# PIC32MK.net
KiCad netlist of a schematic drawn in Altium Designer
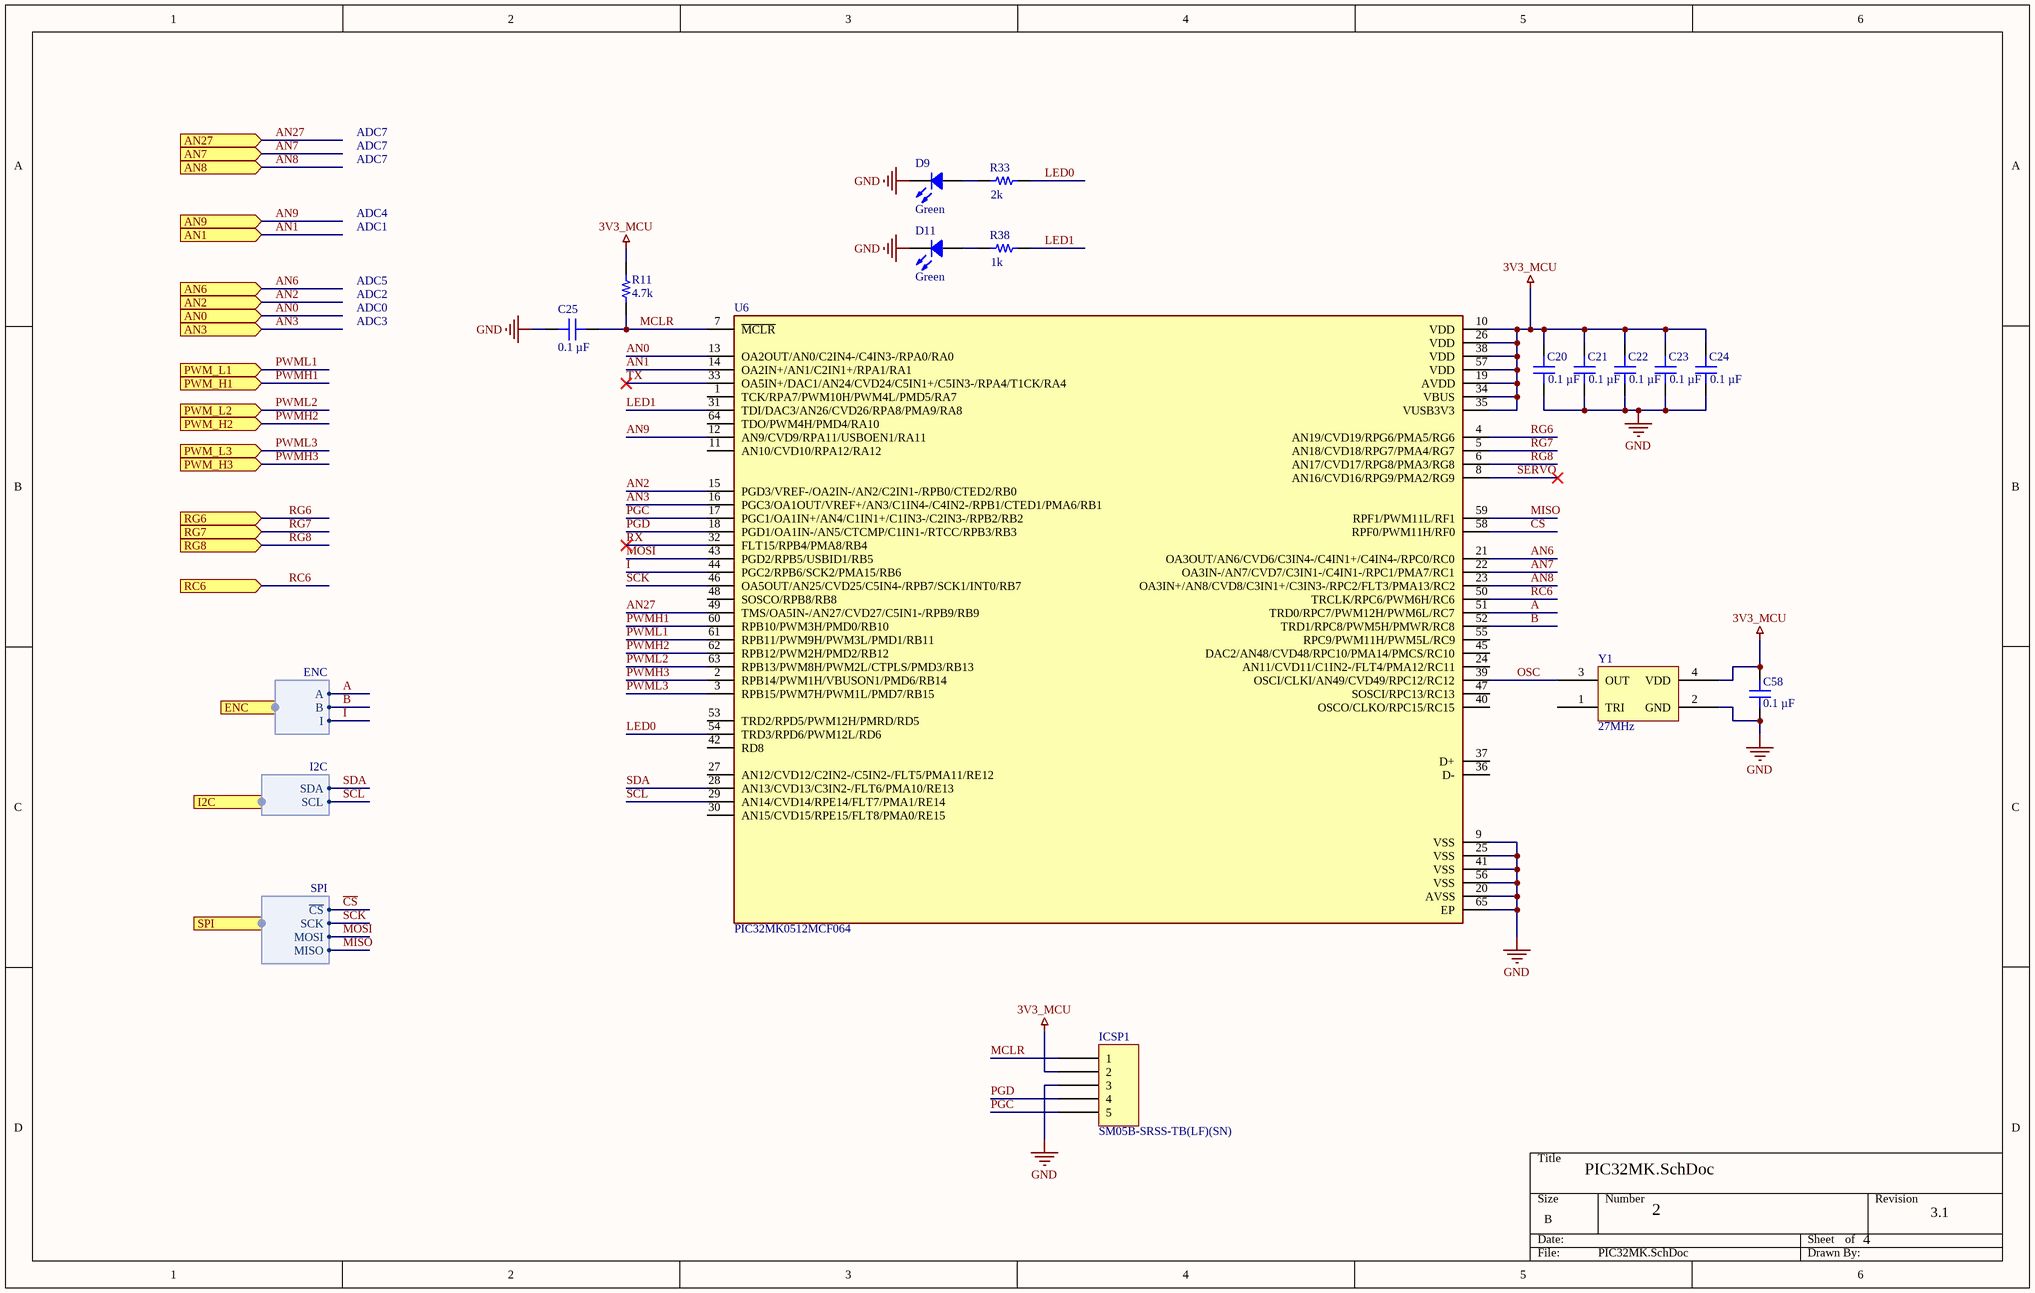
[diagram p0: PIC32MK.SchDoc]

(export (version "E")
  (design (tool "Eeschema 10.0.6"))
  (components
    (comp (ref "C20")
      (value "0.1 µF")
      (footprint "CAP 0402_1005")
      (description "CAP CER 0.1UF 16V X7R 0402")
      (fields (field (name "PART NUMBER") "C0402C104K4RACAUTO") (field (name "MANUFACTURER") "KEMET"))
      (libsource (lib "Celestial Altium Library - altium_library") (part "Capacitor"))
    )
    (comp (ref "C21")
      (value "0.1 µF")
      (footprint "CAP 0402_1005")
      (description "CAP CER 0.1UF 16V X7R 0402")
      (fields (field (name "PART NUMBER") "C0402C104K4RACAUTO") (field (name "MANUFACTURER") "KEMET"))
      (libsource (lib "Celestial Altium Library - altium_library") (part "Capacitor"))
    )
    (comp (ref "C22")
      (value "0.1 µF")
      (footprint "CAP 0402_1005")
      (description "CAP CER 0.1UF 16V X7R 0402")
      (fields (field (name "PART NUMBER") "C0402C104K4RACAUTO") (field (name "MANUFACTURER") "KEMET"))
      (libsource (lib "Celestial Altium Library - altium_library") (part "Capacitor"))
    )
    (comp (ref "C23")
      (value "0.1 µF")
      (footprint "CAP 0402_1005")
      (description "CAP CER 0.1UF 16V X7R 0402")
      (fields (field (name "PART NUMBER") "C0402C104K4RACAUTO") (field (name "MANUFACTURER") "KEMET"))
      (libsource (lib "Celestial Altium Library - altium_library") (part "Capacitor"))
    )
    (comp (ref "C24")
      (value "0.1 µF")
      (footprint "CAP 0402_1005")
      (description "CAP CER 0.1UF 16V X7R 0402")
      (fields (field (name "PART NUMBER") "C0402C104K4RACAUTO") (field (name "MANUFACTURER") "KEMET"))
      (libsource (lib "Celestial Altium Library - altium_library") (part "Capacitor"))
    )
    (comp (ref "C25")
      (value "0.1 µF")
      (footprint "CAP 0402_1005")
      (description "CAP CER 0.1UF 16V X7R 0402")
      (fields (field (name "PART NUMBER") "C0402C104K4RACAUTO") (field (name "MANUFACTURER") "KEMET"))
      (libsource (lib "Celestial Altium Library - altium_library") (part "Capacitor"))
    )
    (comp (ref "C58")
      (value "0.1 µF")
      (footprint "CAP 0402_1005")
      (description "CAP CER 0.1UF 16V X7R 0402")
      (fields (field (name "PART NUMBER") "C0402C104K4RACAUTO") (field (name "MANUFACTURER") "KEMET"))
      (libsource (lib "Celestial Altium Library - altium_library") (part "Capacitor"))
    )
    (comp (ref "D9")
      (value "Green")
      (footprint "LED 0603_1608 GREEN")
      (description "LED GREEN CLEAR 2SMD")
      (fields (field (name "PART NUMBER") "XZCDGK53W-8VF") (field (name "MANUFACTURER") "SunLED"))
      (libsource (lib "Celestial Altium Library - altium_library") (part "LED"))
    )
    (comp (ref "D11")
      (value "Green")
      (footprint "LED 0603_1608 GREEN")
      (description "LED GREEN CLEAR 2SMD")
      (fields (field (name "PART NUMBER") "XZCDGK53W-8VF") (field (name "MANUFACTURER") "SunLED"))
      (libsource (lib "Celestial Altium Library - altium_library") (part "LED"))
    )
    (comp (ref "ICSP1")
      (value "SM05B-SRSS-TB(LF)(SN)")
      (footprint "JST SM05B-SRSS-TB")
      (description "CONN HEADER SMD R/A 5POS 1MM")
      (fields (field (name "MANUFACTURER") "JST Sales America Inc."))
      (libsource (lib "Celestial Altium Library - altium_library") (part "5 Pin"))
    )
    (comp (ref "R11")
      (value "4.7k")
      (footprint "RES_0402")
      (description "RES 0402")
      (libsource (lib "IC") (part "RES_0402"))
    )
    (comp (ref "R33")
      (value "2k")
      (footprint "RES_0402")
      (description "RES 0402")
      (libsource (lib "IC") (part "RES_0402"))
    )
    (comp (ref "R38")
      (value "1k")
      (footprint "RES_0402")
      (description "RES 0402")
      (libsource (lib "IC") (part "RES_0402"))
    )
    (comp (ref "U6")
      (value "PIC32MK0512MCF064")
      (footprint "QFN50P900X900X100-65N")
      (description "PIC32MK Microcontroller IC 32-Bit 120MHz 1MB _1M x 8_ FLASH 64-TQFP _10x10_")
      (fields
        (field (name "MP") "PIC32MK1024MCF064-I/PT")
        (field (name "DIGI-KEY_PART_NUMBER") "PIC32MK1024MCF064-I/PT-ND")
      )
      (libsource (lib "IC") (part "PIC32MK0512MCF064"))
    )
    (comp (ref "Y1")
      (value "27MHz")
      (footprint "ABRACON ASD")
      (description "XTAL OSC XO 27.0000MHZ HCMOS SMD")
      (fields (field (name "PART NUMBER") "ASD3-27.000MHZ-EC-T") (field (name "MANUFACTURER") "Abracon LLC"))
      (libsource (lib "Celestial Altium Library - altium_library") (part "Abracon XO ASD"))
    )
  )
  (nets
    (net (code "4") (name "/A") (class "Default")
      (node (ref "U6") (pin "51") (pinfunction "TRD0/RPC7/PWM12H/PWM6L/RC7_51") (pintype "passive"))
    )
    (net (code "5") (name "/AN0") (class "Default")
      (node (ref "U6") (pin "13") (pinfunction "OA2OUT/AN0/C2IN4-/C4IN3-/RPA0/RA0_13") (pintype "passive"))
    )
    (net (code "6") (name "/AN1") (class "Default")
      (node (ref "U6") (pin "14") (pinfunction "OA2IN+/AN1/C2IN1+/RPA1/RA1_14") (pintype "passive"))
    )
    (net (code "7") (name "/AN2") (class "Default")
      (node (ref "U6") (pin "15") (pinfunction "PGD3/VREF-/OA2IN-/AN2/C2IN1-/RPB0/CTED2/RB0_15") (pintype "passive"))
    )
    (net (code "8") (name "/AN3") (class "Default")
      (node (ref "U6") (pin "16") (pinfunction "PGC3/OA1OUT/VREF+/AN3/C1IN4-/C4IN2-/RPB1/CTED1/PMA6/RB1_16") (pintype "passive"))
    )
    (net (code "9") (name "/AN6") (class "Default")
      (node (ref "U6") (pin "21") (pinfunction "OA3OUT/AN6/CVD6/C3IN4-/C4IN1+/C4IN4-/RPC0/RC0_21") (pintype "passive"))
    )
    (net (code "10") (name "/AN7") (class "Default")
      (node (ref "U6") (pin "22") (pinfunction "OA3IN-/AN7/CVD7/C3IN1-/C4IN1-/RPC1/PMA7/RC1_22") (pintype "passive"))
    )
    (net (code "11") (name "/AN8") (class "Default")
      (node (ref "U6") (pin "23") (pinfunction "OA3IN+/AN8/CVD8/C3IN1+/C3IN3-/RPC2/FLT3/PMA13/RC2_23") (pintype "passive"))
    )
    (net (code "12") (name "/AN9") (class "Default")
      (node (ref "U6") (pin "12") (pinfunction "AN9/CVD9/RPA11/USBOEN1/RA11_12") (pintype "passive"))
    )
    (net (code "13") (name "/AN27") (class "Default")
      (node (ref "U6") (pin "49") (pinfunction "TMS/OA5IN-/AN27/CVD27/C5IN1-/RPB9/RB9_49") (pintype "passive"))
    )
    (net (code "14") (name "/B") (class "Default")
      (node (ref "U6") (pin "52") (pinfunction "TRD1/RPC8/PWM5H/PMWR/RC8_52") (pintype "passive"))
    )
    (net (code "15") (name "/I") (class "Default")
      (node (ref "U6") (pin "44") (pinfunction "PGC2/RPB6/SCK2/PMA15/RB6_44") (pintype "passive"))
    )
    (net (code "16") (name "/LED0") (class "Default")
      (node (ref "R33") (pin "2") (pinfunction "2_2") (pintype "passive"))
      (node (ref "U6") (pin "54") (pinfunction "TRD3/RPD6/PWM12L/RD6_54") (pintype "passive"))
    )
    (net (code "17") (name "/LED1") (class "Default")
      (node (ref "R38") (pin "2") (pinfunction "2_2") (pintype "passive"))
      (node (ref "U6") (pin "31") (pinfunction "TDI/DAC3/AN26/CVD26/RPA8/PMA9/RA8_31") (pintype "passive"))
    )
    (net (code "18") (name "/MCLR") (class "Default")
      (node (ref "C25") (pin "1") (pinfunction "1_1") (pintype "passive"))
      (node (ref "ICSP1") (pin "1") (pinfunction "1_1") (pintype "passive"))
      (node (ref "R11") (pin "1") (pinfunction "1_1") (pintype "passive"))
      (node (ref "U6") (pin "7") (pinfunction "~{MCLR}_7") (pintype "passive"))
    )
    (net (code "19") (name "/MISO") (class "Default")
      (node (ref "U6") (pin "59") (pinfunction "RPF1/PWM11L/RF1_59") (pintype "passive"))
    )
    (net (code "20") (name "/MOSI") (class "Default")
      (node (ref "U6") (pin "43") (pinfunction "PGD2/RPB5/USBID1/RB5_43") (pintype "passive"))
    )
    (net (code "21") (name "/OSC") (class "Default")
      (node (ref "U6") (pin "39") (pinfunction "OSCI/CLKI/AN49/CVD49/RPC12/RC12_39") (pintype "passive"))
      (node (ref "Y1") (pin "3") (pinfunction "OUT_3") (pintype "passive"))
    )
    (net (code "22") (name "/PGC") (class "Default")
      (node (ref "ICSP1") (pin "5") (pinfunction "5_5") (pintype "passive"))
      (node (ref "U6") (pin "17") (pinfunction "PGC1/OA1IN+/AN4/C1IN1+/C1IN3-/C2IN3-/RPB2/RB2_17") (pintype "passive"))
    )
    (net (code "23") (name "/PGD") (class "Default")
      (node (ref "ICSP1") (pin "4") (pinfunction "4_4") (pintype "passive"))
      (node (ref "U6") (pin "18") (pinfunction "PGD1/OA1IN-/AN5/CTCMP/C1IN1-/RTCC/RPB3/RB3_18") (pintype "passive"))
    )
    (net (code "24") (name "/PWMH1") (class "Default")
      (node (ref "U6") (pin "60") (pinfunction "RPB10/PWM3H/PMD0/RB10_60") (pintype "passive"))
    )
    (net (code "25") (name "/PWMH2") (class "Default")
      (node (ref "U6") (pin "62") (pinfunction "RPB12/PWM2H/PMD2/RB12_62") (pintype "passive"))
    )
    (net (code "26") (name "/PWMH3") (class "Default")
      (node (ref "U6") (pin "2") (pinfunction "RPB14/PWM1H/VBUSON1/PMD6/RB14_2") (pintype "passive"))
    )
    (net (code "27") (name "/PWML1") (class "Default")
      (node (ref "U6") (pin "61") (pinfunction "RPB11/PWM9H/PWM3L/PMD1/RB11_61") (pintype "passive"))
    )
    (net (code "28") (name "/PWML2") (class "Default")
      (node (ref "U6") (pin "63") (pinfunction "RPB13/PWM8H/PWM2L/CTPLS/PMD3/RB13_63") (pintype "passive"))
    )
    (net (code "29") (name "/PWML3") (class "Default")
      (node (ref "U6") (pin "3") (pinfunction "RPB15/PWM7H/PWM1L/PMD7/RB15_3") (pintype "passive"))
    )
    (net (code "30") (name "/RC6") (class "Default")
      (node (ref "U6") (pin "50") (pinfunction "TRCLK/RPC6/PWM6H/RC6_50") (pintype "passive"))
    )
    (net (code "31") (name "/RG6") (class "Default")
      (node (ref "U6") (pin "4") (pinfunction "AN19/CVD19/RPG6/PMA5/RG6_4") (pintype "passive"))
    )
    (net (code "32") (name "/RG7") (class "Default")
      (node (ref "U6") (pin "5") (pinfunction "AN18/CVD18/RPG7/PMA4/RG7_5") (pintype "passive"))
    )
    (net (code "33") (name "/RG8") (class "Default")
      (node (ref "U6") (pin "6") (pinfunction "AN17/CVD17/RPG8/PMA3/RG8_6") (pintype "passive"))
    )
    (net (code "34") (name "/RX") (class "Default")
      (node (ref "U6") (pin "32") (pinfunction "FLT15/RPB4/PMA8/RB4_32") (pintype "passive+no_connect"))
    )
    (net (code "35") (name "/SCK") (class "Default")
      (node (ref "U6") (pin "46") (pinfunction "OA5OUT/AN25/CVD25/C5IN4-/RPB7/SCK1/INT0/RB7_46") (pintype "passive"))
    )
    (net (code "36") (name "/SCL") (class "Default")
      (node (ref "U6") (pin "29") (pinfunction "AN14/CVD14/RPE14/FLT7/PMA1/RE14_29") (pintype "passive"))
    )
    (net (code "37") (name "/SDA") (class "Default")
      (node (ref "U6") (pin "28") (pinfunction "AN13/CVD13/C3IN2-/FLT6/PMA10/RE13_28") (pintype "passive"))
    )
    (net (code "38") (name "/SERVO") (class "Default")
      (node (ref "U6") (pin "8") (pinfunction "AN16/CVD16/RPG9/PMA2/RG9_8") (pintype "passive+no_connect"))
    )
    (net (code "39") (name "/TX") (class "Default")
      (node (ref "U6") (pin "33") (pinfunction "OA5IN+/DAC1/AN24/CVD24/C5IN1+/C5IN3-/RPA4/T1CK/RA4_33") (pintype "passive+no_connect"))
    )
    (net (code "43") (name "/~{CS}") (class "Default")
      (node (ref "U6") (pin "58") (pinfunction "RPF0/PWM11H/RF0_58") (pintype "passive"))
    )
    (net (code "44") (name "3V3_MCU") (class "Default")
      (node (ref "C20") (pin "2") (pinfunction "2_2") (pintype "passive"))
      (node (ref "C21") (pin "2") (pinfunction "2_2") (pintype "passive"))
      (node (ref "C22") (pin "2") (pinfunction "2_2") (pintype "passive"))
      (node (ref "C23") (pin "2") (pinfunction "2_2") (pintype "passive"))
      (node (ref "C24") (pin "2") (pinfunction "2_2") (pintype "passive"))
      (node (ref "C58") (pin "2") (pinfunction "2_2") (pintype "passive"))
      (node (ref "ICSP1") (pin "2") (pinfunction "2_2") (pintype "passive"))
      (node (ref "R11") (pin "2") (pinfunction "2_2") (pintype "passive"))
      (node (ref "U6") (pin "10") (pinfunction "VDD_10") (pintype "power_in"))
      (node (ref "U6") (pin "19") (pinfunction "AVDD_19") (pintype "power_in"))
      (node (ref "U6") (pin "26") (pinfunction "VDD_26") (pintype "power_in"))
      (node (ref "U6") (pin "34") (pinfunction "VBUS_34") (pintype "power_in"))
      (node (ref "U6") (pin "35") (pinfunction "VUSB3V3_35") (pintype "passive"))
      (node (ref "U6") (pin "38") (pinfunction "VDD_38") (pintype "power_in"))
      (node (ref "U6") (pin "57") (pinfunction "VDD_57") (pintype "power_in"))
      (node (ref "Y1") (pin "4") (pinfunction "VDD_4") (pintype "passive"))
    )
    (net (code "45") (name "GND") (class "Default")
      (node (ref "C20") (pin "1") (pinfunction "1_1") (pintype "passive"))
      (node (ref "C21") (pin "1") (pinfunction "1_1") (pintype "passive"))
      (node (ref "C22") (pin "1") (pinfunction "1_1") (pintype "passive"))
      (node (ref "C23") (pin "1") (pinfunction "1_1") (pintype "passive"))
      (node (ref "C24") (pin "1") (pinfunction "1_1") (pintype "passive"))
      (node (ref "C25") (pin "2") (pinfunction "2_2") (pintype "passive"))
      (node (ref "C58") (pin "1") (pinfunction "1_1") (pintype "passive"))
      (node (ref "D11") (pin "2") (pinfunction "2_2") (pintype "passive"))
      (node (ref "D9") (pin "2") (pinfunction "2_2") (pintype "passive"))
      (node (ref "ICSP1") (pin "3") (pinfunction "3_3") (pintype "passive"))
      (node (ref "U6") (pin "20") (pinfunction "AVSS_20") (pintype "power_in"))
      (node (ref "U6") (pin "25") (pinfunction "VSS_25") (pintype "power_in"))
      (node (ref "U6") (pin "41") (pinfunction "VSS_41") (pintype "power_in"))
      (node (ref "U6") (pin "56") (pinfunction "VSS_56") (pintype "power_in"))
      (node (ref "U6") (pin "65") (pinfunction "EP_65") (pintype "power_in"))
      (node (ref "U6") (pin "9") (pinfunction "VSS_9") (pintype "power_in"))
      (node (ref "Y1") (pin "2") (pinfunction "GND_2") (pintype "passive"))
    )
    (net (code "46") (name "Net-(D9-Pad1)") (class "Default")
      (node (ref "D9") (pin "1") (pinfunction "1_1") (pintype "passive"))
      (node (ref "R33") (pin "1") (pinfunction "1_1") (pintype "passive"))
    )
    (net (code "47") (name "Net-(D11-Pad1)") (class "Default")
      (node (ref "D11") (pin "1") (pinfunction "1_1") (pintype "passive"))
      (node (ref "R38") (pin "1") (pinfunction "1_1") (pintype "passive"))
    )
    (net (code "48") (name "unconnected-(U6-AN10{slash}CVD10{slash}RPA12{slash}RA12-Pad11)") (class "Default")
      (node (ref "U6") (pin "11") (pinfunction "AN10/CVD10/RPA12/RA12_11") (pintype "passive"))
    )
    (net (code "49") (name "unconnected-(U6-AN11{slash}CVD11{slash}C1IN2-{slash}FLT4{slash}PMA12{slash}RC11-Pad24)") (class "Default")
      (node (ref "U6") (pin "24") (pinfunction "AN11/CVD11/C1IN2-/FLT4/PMA12/RC11_24") (pintype "passive"))
    )
    (net (code "50") (name "unconnected-(U6-AN12{slash}CVD12{slash}C2IN2-{slash}C5IN2-{slash}FLT5{slash}PMA11{slash}RE12-Pad27)") (class "Default")
      (node (ref "U6") (pin "27") (pinfunction "AN12/CVD12/C2IN2-/C5IN2-/FLT5/PMA11/RE12_27") (pintype "passive"))
    )
    (net (code "51") (name "unconnected-(U6-AN15{slash}CVD15{slash}RPE15{slash}FLT8{slash}PMA0{slash}RE15-Pad30)") (class "Default")
      (node (ref "U6") (pin "30") (pinfunction "AN15/CVD15/RPE15/FLT8/PMA0/RE15_30") (pintype "passive"))
    )
    (net (code "52") (name "unconnected-(U6-D+-Pad37)") (class "Default")
      (node (ref "U6") (pin "37") (pinfunction "D+_37") (pintype "passive"))
    )
    (net (code "53") (name "unconnected-(U6-D--Pad36)") (class "Default")
      (node (ref "U6") (pin "36") (pinfunction "D-_36") (pintype "passive"))
    )
    (net (code "54") (name "unconnected-(U6-DAC2{slash}AN48{slash}CVD48{slash}RPC10{slash}PMA14{slash}PMCS{slash}RC10-Pad45)") (class "Default")
      (node (ref "U6") (pin "45") (pinfunction "DAC2/AN48/CVD48/RPC10/PMA14/PMCS/RC10_45") (pintype "passive"))
    )
    (net (code "55") (name "unconnected-(U6-OSCO{slash}CLKO{slash}RPC15{slash}RC15-Pad40)") (class "Default")
      (node (ref "U6") (pin "40") (pinfunction "OSCO/CLKO/RPC15/RC15_40") (pintype "passive"))
    )
    (net (code "56") (name "unconnected-(U6-RD8-Pad42)") (class "Default")
      (node (ref "U6") (pin "42") (pinfunction "RD8_42") (pintype "passive"))
    )
    (net (code "57") (name "unconnected-(U6-RPC9{slash}PWM11H{slash}PWM5L{slash}RC9-Pad55)") (class "Default")
      (node (ref "U6") (pin "55") (pinfunction "RPC9/PWM11H/PWM5L/RC9_55") (pintype "passive"))
    )
    (net (code "58") (name "unconnected-(U6-SOSCI{slash}RPC13{slash}RC13-Pad47)") (class "Default")
      (node (ref "U6") (pin "47") (pinfunction "SOSCI/RPC13/RC13_47") (pintype "passive"))
    )
    (net (code "59") (name "unconnected-(U6-SOSCO{slash}RPB8{slash}RB8-Pad48)") (class "Default")
      (node (ref "U6") (pin "48") (pinfunction "SOSCO/RPB8/RB8_48") (pintype "passive"))
    )
    (net (code "60") (name "unconnected-(U6-TCK{slash}RPA7{slash}PWM10H{slash}PWM4L{slash}PMD5{slash}RA7-Pad1)") (class "Default")
      (node (ref "U6") (pin "1") (pinfunction "TCK/RPA7/PWM10H/PWM4L/PMD5/RA7_1") (pintype "passive"))
    )
    (net (code "61") (name "unconnected-(U6-TDO{slash}PWM4H{slash}PMD4{slash}RA10-Pad64)") (class "Default")
      (node (ref "U6") (pin "64") (pinfunction "TDO/PWM4H/PMD4/RA10_64") (pintype "passive"))
    )
    (net (code "62") (name "unconnected-(U6-TRD2{slash}RPD5{slash}PWM12H{slash}PMRD{slash}RD5-Pad53)") (class "Default")
      (node (ref "U6") (pin "53") (pinfunction "TRD2/RPD5/PWM12H/PMRD/RD5_53") (pintype "passive"))
    )
    (net (code "63") (name "unconnected-(Y1-TRI-Pad1)") (class "Default")
      (node (ref "Y1") (pin "1") (pinfunction "TRI_1") (pintype "passive"))
    )
  )
)
